# PCM2706_PCM5102A.net
KiCad netlist of a schematic drawn in EAGLE
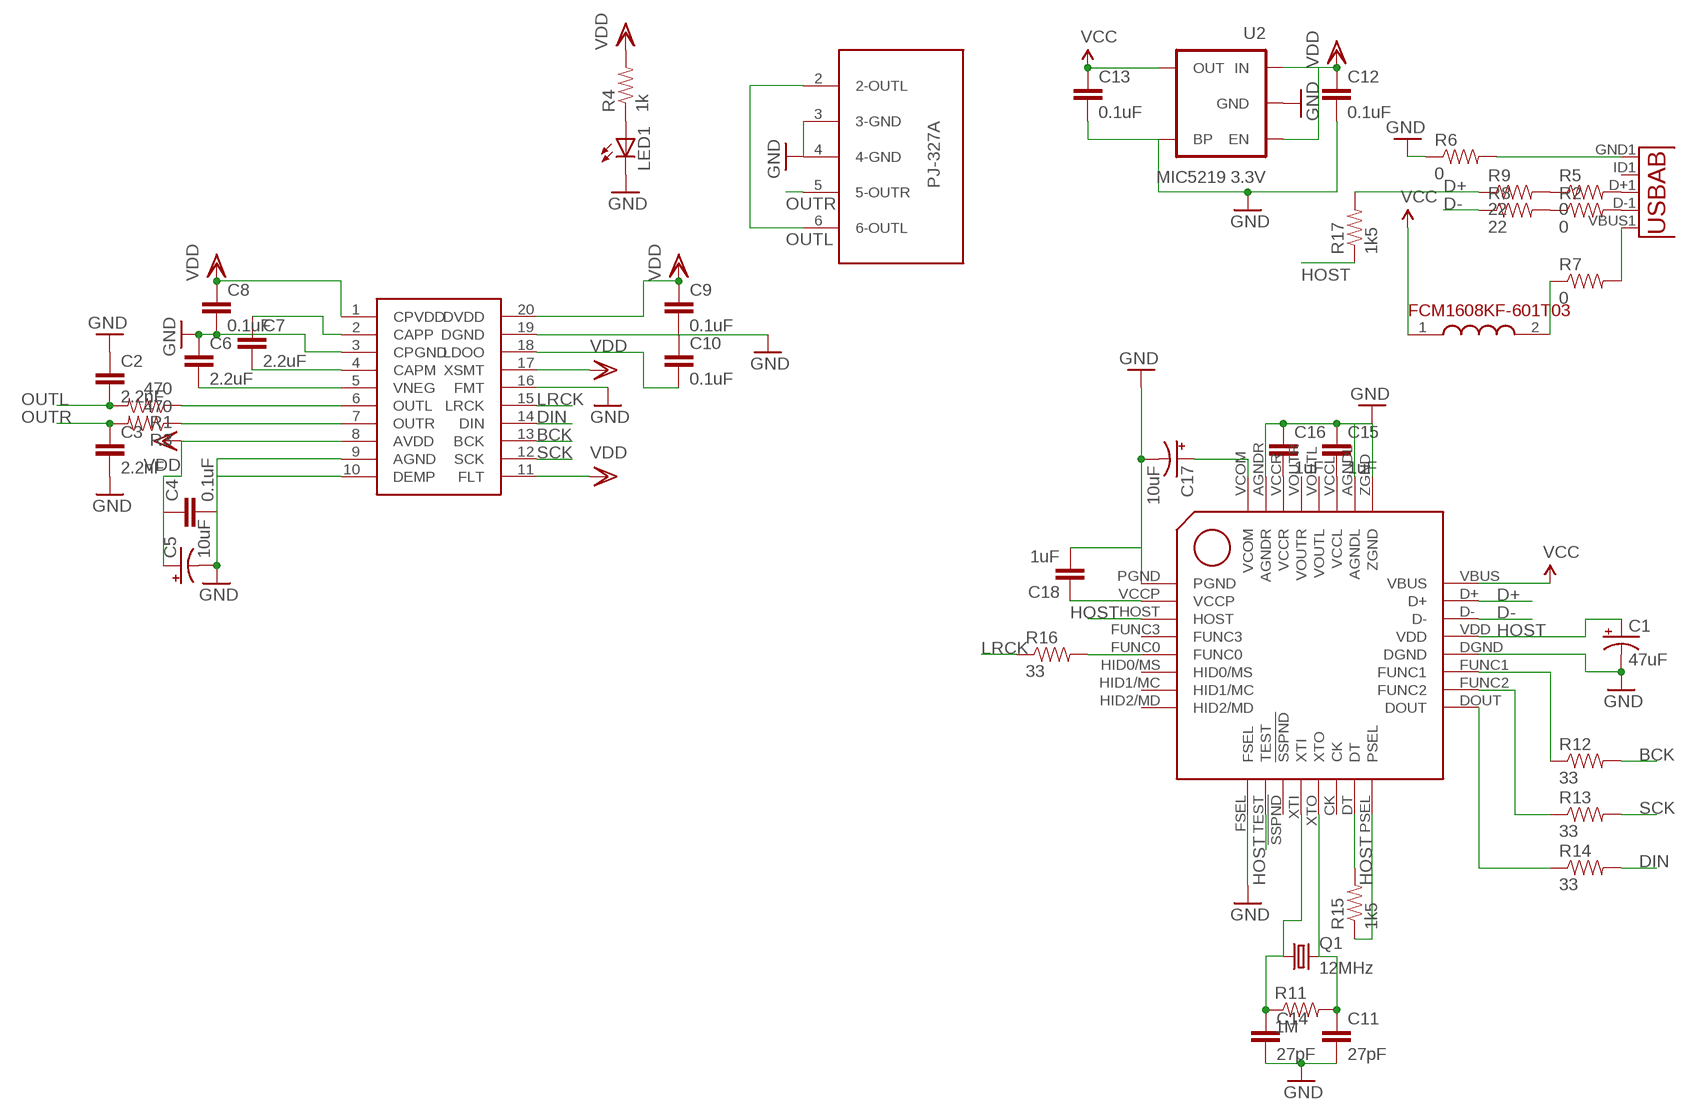
[diagram p0: schematic, sheet 1]

(export (version "E")
  (design (tool "Eeschema 10.0.6"))
  (components
    (comp (ref "C1")
      (value "47uF")
      (footprint "eagle-import:NIPPON_F80")
      (libsource (lib "eagle-import") (part "CAP_POLF80"))
    )
    (comp (ref "C2")
      (value "2.2nF")
      (footprint "eagle-import:C5B2.5")
      (libsource (lib "eagle-import") (part "C5/2.5"))
    )
    (comp (ref "C3")
      (value "2.2nF")
      (footprint "eagle-import:C5B2.5")
      (libsource (lib "eagle-import") (part "C5/2.5"))
    )
    (comp (ref "C4")
      (value "0.1uF")
      (footprint "eagle-import:1206")
      (libsource (lib "eagle-import") (part "2.2UF-CERCAP-10009"))
    )
    (comp (ref "C5")
      (value "10uF")
      (footprint "eagle-import:NIPPON_F80")
      (libsource (lib "eagle-import") (part "CAP_POLF80"))
    )
    (comp (ref "C6")
      (value "2.2uF")
      (footprint "eagle-import:1206")
      (libsource (lib "eagle-import") (part "2.2UF-CERCAP-10009"))
    )
    (comp (ref "C7")
      (value "2.2uF")
      (footprint "eagle-import:1206")
      (libsource (lib "eagle-import") (part "2.2UF-CERCAP-10009"))
    )
    (comp (ref "C8")
      (value "0.1uF")
      (footprint "eagle-import:1206")
      (libsource (lib "eagle-import") (part "2.2UF-CERCAP-10009"))
    )
    (comp (ref "C9")
      (value "0.1uF")
      (footprint "eagle-import:1206")
      (libsource (lib "eagle-import") (part "2.2UF-CERCAP-10009"))
    )
    (comp (ref "C10")
      (value "0.1uF")
      (footprint "eagle-import:1206")
      (libsource (lib "eagle-import") (part "2.2UF-CERCAP-10009"))
    )
    (comp (ref "C11")
      (value "27pF")
      (footprint "eagle-import:1206")
      (libsource (lib "eagle-import") (part "2.2UF-CERCAP-10009"))
    )
    (comp (ref "C12")
      (value "0.1uF")
      (footprint "eagle-import:1206")
      (libsource (lib "eagle-import") (part "2.2UF-CERCAP-10009"))
    )
    (comp (ref "C13")
      (value "0.1uF")
      (footprint "eagle-import:1206")
      (libsource (lib "eagle-import") (part "2.2UF-CERCAP-10009"))
    )
    (comp (ref "C14")
      (value "27pF")
      (footprint "eagle-import:1206")
      (libsource (lib "eagle-import") (part "2.2UF-CERCAP-10009"))
    )
    (comp (ref "C15")
      (value "1uF")
      (footprint "eagle-import:1206")
      (libsource (lib "eagle-import") (part "2.2UF-CERCAP-10009"))
    )
    (comp (ref "C16")
      (value "1uF")
      (footprint "eagle-import:1206")
      (libsource (lib "eagle-import") (part "2.2UF-CERCAP-10009"))
    )
    (comp (ref "C17")
      (value "10uF")
      (footprint "eagle-import:NIPPON_F80")
      (libsource (lib "eagle-import") (part "CAP_POLF80"))
    )
    (comp (ref "C18")
      (value "1uF")
      (footprint "eagle-import:1206")
      (libsource (lib "eagle-import") (part "2.2UF-CERCAP-10009"))
    )
    (comp (ref "LED1")
      (value "LEDCHIP-LED0805")
      (footprint "eagle-import:CHIP-LED0805")
      (libsource (lib "eagle-import") (part "LEDCHIP-LED0805"))
    )
    (comp (ref "Q1")
      (value "12MHz")
      (footprint "eagle-import:SM49")
      (libsource (lib "eagle-import") (part "CRYSTALSM49"))
    )
    (comp (ref "R1")
      (value "470")
      (footprint "eagle-import:1206")
      (libsource (lib "eagle-import") (part "RESISTOR1206"))
    )
    (comp (ref "R2")
      (value "0")
      (footprint "eagle-import:0805")
      (libsource (lib "eagle-import") (part "RESISTOR0805-RES"))
    )
    (comp (ref "R3")
      (value "470")
      (footprint "eagle-import:1206")
      (libsource (lib "eagle-import") (part "RESISTOR1206"))
    )
    (comp (ref "R4")
      (value "1k")
      (footprint "eagle-import:1206")
      (libsource (lib "eagle-import") (part "RESISTOR1206"))
    )
    (comp (ref "R5")
      (value "0")
      (footprint "eagle-import:0805")
      (libsource (lib "eagle-import") (part "RESISTOR0805-RES"))
    )
    (comp (ref "R6")
      (value "0")
      (footprint "eagle-import:0805")
      (libsource (lib "eagle-import") (part "RESISTOR0805-RES"))
    )
    (comp (ref "R7")
      (value "0")
      (footprint "eagle-import:0805")
      (libsource (lib "eagle-import") (part "RESISTOR0805-RES"))
    )
    (comp (ref "R8")
      (value "22")
      (footprint "eagle-import:0805")
      (libsource (lib "eagle-import") (part "RESISTOR0805-RES"))
    )
    (comp (ref "R9")
      (value "22")
      (footprint "eagle-import:0805")
      (libsource (lib "eagle-import") (part "RESISTOR0805-RES"))
    )
    (comp (ref "R11")
      (value "1M")
      (footprint "eagle-import:0805")
      (libsource (lib "eagle-import") (part "RESISTOR0805-RES"))
    )
    (comp (ref "R12")
      (value "33")
      (footprint "eagle-import:0805")
      (libsource (lib "eagle-import") (part "RESISTOR0805-RES"))
    )
    (comp (ref "R13")
      (value "33")
      (footprint "eagle-import:0805")
      (libsource (lib "eagle-import") (part "RESISTOR0805-RES"))
    )
    (comp (ref "R14")
      (value "33")
      (footprint "eagle-import:0805")
      (libsource (lib "eagle-import") (part "RESISTOR0805-RES"))
    )
    (comp (ref "R15")
      (value "1k5")
      (footprint "eagle-import:0805")
      (libsource (lib "eagle-import") (part "RESISTOR0805-RES"))
    )
    (comp (ref "R16")
      (value "33")
      (footprint "eagle-import:0805")
      (libsource (lib "eagle-import") (part "RESISTOR0805-RES"))
    )
    (comp (ref "R17")
      (value "1k5")
      (footprint "eagle-import:0805")
      (libsource (lib "eagle-import") (part "RESISTOR0805-RES"))
    )
    (comp (ref "U$1")
      (value "PCM5102")
      (footprint "eagle-import:TSSOP20")
      (libsource (lib "eagle-import") (part "PCM5102"))
    )
    (comp (ref "U$2")
      (value "PJ-327A")
      (footprint "eagle-import:PJ-327A")
      (libsource (lib "eagle-import") (part "PJ-327A"))
    )
    (comp (ref "U$3")
      (value "PCM2706")
      (footprint "eagle-import:TQFP32-08")
      (libsource (lib "eagle-import") (part "PCM2706"))
    )
    (comp (ref "U$4")
      (value "FCM1608KF-601T03")
      (footprint "eagle-import:FCM1608KF-601T03")
      (libsource (lib "eagle-import") (part "FCM1608KF-601T03"))
    )
    (comp (ref "U1")
      (value "USB\"\"")
      (footprint "eagle-import:USB-MICRO-SMD")
      (libsource (lib "eagle-import") (part "USB{dblquote}{dblquote}"))
    )
    (comp (ref "U2")
      (value "MIC5219 3.3V")
      (footprint "eagle-import:SOT23-5")
      (libsource (lib "eagle-import") (part "V_REG_MIC52193.3V"))
    )
  )
  (nets
    (net (code "1") (name "/BCK") (class "Default")
      (node (ref "R12") (pin "2") (pinfunction "2_2") (pintype "passive"))
      (node (ref "U$1") (pin "13") (pinfunction "BCK_13") (pintype "bidirectional"))
    )
    (net (code "2") (name "/D+") (class "Default")
      (node (ref "R17") (pin "2") (pinfunction "2_2") (pintype "passive"))
      (node (ref "R9") (pin "1") (pinfunction "1_1") (pintype "passive"))
      (node (ref "U$3") (pin "D+") (pinfunction "D+_D+") (pintype "bidirectional"))
    )
    (net (code "3") (name "/D-") (class "Default")
      (node (ref "R8") (pin "1") (pinfunction "1_1") (pintype "passive"))
      (node (ref "U$3") (pin "D-") (pinfunction "D-_D-") (pintype "bidirectional"))
    )
    (net (code "4") (name "/DIN") (class "Default")
      (node (ref "R14") (pin "2") (pinfunction "2_2") (pintype "passive"))
      (node (ref "U$1") (pin "14") (pinfunction "DIN_14") (pintype "bidirectional"))
    )
    (net (code "5") (name "/HOST") (class "Default")
      (node (ref "C1") (pin "+") (pinfunction "+_+") (pintype "passive"))
      (node (ref "R15") (pin "1") (pinfunction "1_1") (pintype "passive"))
      (node (ref "R17") (pin "1") (pinfunction "1_1") (pintype "passive"))
      (node (ref "U$3") (pin "HOST") (pinfunction "HOST_HOST") (pintype "power_in"))
      (node (ref "U$3") (pin "PSEL") (pinfunction "PSEL_PSEL") (pintype "bidirectional"))
      (node (ref "U$3") (pin "TEST") (pinfunction "TEST_TEST") (pintype "bidirectional"))
      (node (ref "U$3") (pin "VDD") (pinfunction "VDD_VDD") (pintype "power_in"))
    )
    (net (code "6") (name "/LRCK") (class "Default")
      (node (ref "R16") (pin "1") (pinfunction "1_1") (pintype "passive"))
      (node (ref "U$1") (pin "15") (pinfunction "LRCK_15") (pintype "bidirectional"))
    )
    (net (code "7") (name "/OUTL") (class "Default")
      (node (ref "C2") (pin "2") (pinfunction "2_2") (pintype "passive"))
      (node (ref "R1") (pin "2") (pinfunction "2_2") (pintype "passive"))
      (node (ref "U$2") (pin "2") (pinfunction "2-OUTL_2") (pintype "bidirectional"))
      (node (ref "U$2") (pin "6") (pinfunction "6-OUTL_6") (pintype "bidirectional"))
    )
    (net (code "8") (name "/OUTR") (class "Default")
      (node (ref "C3") (pin "1") (pinfunction "1_1") (pintype "passive"))
      (node (ref "R3") (pin "2") (pinfunction "2_2") (pintype "passive"))
      (node (ref "U$2") (pin "5") (pinfunction "5-OUTR_5") (pintype "bidirectional"))
    )
    (net (code "9") (name "/SCK") (class "Default")
      (node (ref "R13") (pin "2") (pinfunction "2_2") (pintype "passive"))
      (node (ref "U$1") (pin "12") (pinfunction "SCK_12") (pintype "bidirectional"))
    )
    (net (code "10") (name "GND") (class "Default")
      (node (ref "C1") (pin "-") (pinfunction "-_-") (pintype "passive"))
      (node (ref "C10") (pin "1") (pinfunction "1_1") (pintype "passive"))
      (node (ref "C11") (pin "2") (pinfunction "2_2") (pintype "passive"))
      (node (ref "C12") (pin "2") (pinfunction "2_2") (pintype "passive"))
      (node (ref "C13") (pin "2") (pinfunction "2_2") (pintype "passive"))
      (node (ref "C14") (pin "2") (pinfunction "2_2") (pintype "passive"))
      (node (ref "C15") (pin "1") (pinfunction "1_1") (pintype "passive"))
      (node (ref "C16") (pin "1") (pinfunction "1_1") (pintype "passive"))
      (node (ref "C17") (pin "-") (pinfunction "-_-") (pintype "passive"))
      (node (ref "C18") (pin "2") (pinfunction "2_2") (pintype "passive"))
      (node (ref "C2") (pin "1") (pinfunction "1_1") (pintype "passive"))
      (node (ref "C3") (pin "2") (pinfunction "2_2") (pintype "passive"))
      (node (ref "C4") (pin "2") (pinfunction "2_2") (pintype "passive"))
      (node (ref "C5") (pin "-") (pinfunction "-_-") (pintype "passive"))
      (node (ref "C6") (pin "1") (pinfunction "1_1") (pintype "passive"))
      (node (ref "C8") (pin "2") (pinfunction "2_2") (pintype "passive"))
      (node (ref "C9") (pin "2") (pinfunction "2_2") (pintype "passive"))
      (node (ref "LED1") (pin "C") (pinfunction "C_C") (pintype "passive"))
      (node (ref "R6") (pin "1") (pinfunction "1_1") (pintype "passive"))
      (node (ref "U$1") (pin "10") (pinfunction "DEMP_10") (pintype "bidirectional"))
      (node (ref "U$1") (pin "16") (pinfunction "FMT_16") (pintype "bidirectional"))
      (node (ref "U$1") (pin "19") (pinfunction "DGND_19") (pintype "bidirectional"))
      (node (ref "U$1") (pin "3") (pinfunction "CPGND_3") (pintype "bidirectional"))
      (node (ref "U$1") (pin "9") (pinfunction "AGND_9") (pintype "bidirectional"))
      (node (ref "U$2") (pin "3") (pinfunction "3-GND_3") (pintype "bidirectional"))
      (node (ref "U$2") (pin "4") (pinfunction "4-GND_4") (pintype "bidirectional"))
      (node (ref "U$3") (pin "AGNDL") (pinfunction "AGNDL_AGNDL") (pintype "power_in"))
      (node (ref "U$3") (pin "AGNDR") (pinfunction "AGNDR_AGNDR") (pintype "power_in"))
      (node (ref "U$3") (pin "DGND") (pinfunction "DGND_DGND") (pintype "power_in"))
      (node (ref "U$3") (pin "FSEL") (pinfunction "FSEL_FSEL") (pintype "bidirectional"))
      (node (ref "U$3") (pin "PGND") (pinfunction "PGND_PGND") (pintype "power_in"))
      (node (ref "U$3") (pin "ZGND") (pinfunction "ZGND_ZGND") (pintype "power_in"))
      (node (ref "U2") (pin "2") (pinfunction "GND_2") (pintype "input"))
      (node (ref "U2") (pin "4") (pinfunction "BP_4") (pintype "input"))
    )
    (net (code "11") (name "Net-(C11-Pad1)") (class "Default")
      (node (ref "C11") (pin "1") (pinfunction "1_1") (pintype "passive"))
      (node (ref "Q1") (pin "2") (pinfunction "2_2") (pintype "passive"))
      (node (ref "R11") (pin "2") (pinfunction "2_2") (pintype "passive"))
      (node (ref "U$3") (pin "XTO") (pinfunction "XTO_XTO") (pintype "bidirectional"))
    )
    (net (code "12") (name "Net-(C14-Pad1)") (class "Default")
      (node (ref "C14") (pin "1") (pinfunction "1_1") (pintype "passive"))
      (node (ref "Q1") (pin "1") (pinfunction "1_1") (pintype "passive"))
      (node (ref "R11") (pin "1") (pinfunction "1_1") (pintype "passive"))
      (node (ref "U$3") (pin "XTI") (pinfunction "XTI_XTI") (pintype "bidirectional"))
    )
    (net (code "13") (name "Net-(C15-Pad2)") (class "Default")
      (node (ref "C15") (pin "2") (pinfunction "2_2") (pintype "passive"))
      (node (ref "U$3") (pin "VCCL") (pinfunction "VCCL_VCCL") (pintype "power_in"))
    )
    (net (code "14") (name "Net-(C16-Pad2)") (class "Default")
      (node (ref "C16") (pin "2") (pinfunction "2_2") (pintype "passive"))
      (node (ref "U$3") (pin "VCCR") (pinfunction "VCCR_VCCR") (pintype "power_in"))
    )
    (net (code "15") (name "Net-(C17-Pad+)") (class "Default")
      (node (ref "C17") (pin "+") (pinfunction "+_+") (pintype "passive"))
      (node (ref "U$3") (pin "VCOM") (pinfunction "VCOM_VCOM") (pintype "power_in"))
    )
    (net (code "16") (name "Net-(C18-Pad1)") (class "Default")
      (node (ref "C18") (pin "1") (pinfunction "1_1") (pintype "passive"))
      (node (ref "U$3") (pin "VCCP") (pinfunction "VCCP_VCCP") (pintype "power_in"))
    )
    (net (code "17") (name "Net-(LED1-PadA)") (class "Default")
      (node (ref "LED1") (pin "A") (pinfunction "A_A") (pintype "passive"))
      (node (ref "R4") (pin "1") (pinfunction "1_1") (pintype "passive"))
    )
    (net (code "18") (name "Net-(R2-Pad1)") (class "Default")
      (node (ref "R2") (pin "1") (pinfunction "1_1") (pintype "passive"))
      (node (ref "R8") (pin "2") (pinfunction "2_2") (pintype "passive"))
    )
    (net (code "19") (name "Net-(R5-Pad1)") (class "Default")
      (node (ref "R5") (pin "1") (pinfunction "1_1") (pintype "passive"))
      (node (ref "R9") (pin "2") (pinfunction "2_2") (pintype "passive"))
    )
    (net (code "20") (name "Net-(R12-Pad1)") (class "Default")
      (node (ref "R12") (pin "1") (pinfunction "1_1") (pintype "passive"))
      (node (ref "U$3") (pin "FUNC1") (pinfunction "FUNC1_FUNC1") (pintype "bidirectional"))
    )
    (net (code "21") (name "Net-(R13-Pad1)") (class "Default")
      (node (ref "R13") (pin "1") (pinfunction "1_1") (pintype "passive"))
      (node (ref "U$3") (pin "FUNC2") (pinfunction "FUNC2_FUNC2") (pintype "bidirectional"))
    )
    (net (code "22") (name "Net-(R14-Pad1)") (class "Default")
      (node (ref "R14") (pin "1") (pinfunction "1_1") (pintype "passive"))
      (node (ref "U$3") (pin "DOUT") (pinfunction "DOUT_DOUT") (pintype "bidirectional"))
    )
    (net (code "23") (name "Net-(R15-Pad2)") (class "Default")
      (node (ref "R15") (pin "2") (pinfunction "2_2") (pintype "passive"))
      (node (ref "U$3") (pin "DT") (pinfunction "DT_DT") (pintype "bidirectional"))
    )
    (net (code "24") (name "Net-(R16-Pad2)") (class "Default")
      (node (ref "R16") (pin "2") (pinfunction "2_2") (pintype "passive"))
      (node (ref "U$3") (pin "FUNC0") (pinfunction "FUNC0_FUNC0") (pintype "bidirectional"))
    )
    (net (code "25") (name "Net-(U$1-CAPM)") (class "Default")
      (node (ref "C7") (pin "2") (pinfunction "2_2") (pintype "passive"))
      (node (ref "U$1") (pin "4") (pinfunction "CAPM_4") (pintype "bidirectional"))
    )
    (net (code "26") (name "Net-(U$1-CAPP)") (class "Default")
      (node (ref "C7") (pin "1") (pinfunction "1_1") (pintype "passive"))
      (node (ref "U$1") (pin "2") (pinfunction "CAPP_2") (pintype "bidirectional"))
    )
    (net (code "27") (name "Net-(U$1-LDOO)") (class "Default")
      (node (ref "C10") (pin "2") (pinfunction "2_2") (pintype "passive"))
      (node (ref "U$1") (pin "18") (pinfunction "LDOO_18") (pintype "bidirectional"))
    )
    (net (code "28") (name "Net-(U$1-OUTL)") (class "Default")
      (node (ref "R1") (pin "1") (pinfunction "1_1") (pintype "passive"))
      (node (ref "U$1") (pin "6") (pinfunction "OUTL_6") (pintype "bidirectional"))
    )
    (net (code "29") (name "Net-(U$1-OUTR)") (class "Default")
      (node (ref "R3") (pin "1") (pinfunction "1_1") (pintype "passive"))
      (node (ref "U$1") (pin "7") (pinfunction "OUTR_7") (pintype "bidirectional"))
    )
    (net (code "30") (name "Net-(U$1-VNEG)") (class "Default")
      (node (ref "C6") (pin "2") (pinfunction "2_2") (pintype "passive"))
      (node (ref "U$1") (pin "5") (pinfunction "VNEG_5") (pintype "bidirectional"))
    )
    (net (code "31") (name "Net-(U$4-2.OUT)") (class "Default")
      (node (ref "R7") (pin "1") (pinfunction "1_1") (pintype "passive"))
      (node (ref "U$4") (pin "2") (pinfunction "2.OUT_2") (pintype "bidirectional"))
    )
    (net (code "32") (name "Net-(U1-D+)") (class "Default")
      (node (ref "R5") (pin "2") (pinfunction "2_2") (pintype "passive"))
      (node (ref "U1") (pin "D+1") (pinfunction "D+_D+1") (pintype "bidirectional"))
    )
    (net (code "33") (name "Net-(U1-D-)") (class "Default")
      (node (ref "R2") (pin "2") (pinfunction "2_2") (pintype "passive"))
      (node (ref "U1") (pin "D-1") (pinfunction "D-_D-1") (pintype "bidirectional"))
    )
    (net (code "34") (name "Net-(U1-GND)") (class "Default")
      (node (ref "R6") (pin "2") (pinfunction "2_2") (pintype "passive"))
      (node (ref "U1") (pin "GND1") (pinfunction "GND_GND1") (pintype "bidirectional"))
    )
    (net (code "35") (name "Net-(U1-VBUS)") (class "Default")
      (node (ref "R7") (pin "2") (pinfunction "2_2") (pintype "passive"))
      (node (ref "U1") (pin "VBUS1") (pinfunction "VBUS_VBUS1") (pintype "bidirectional"))
    )
    (net (code "36") (name "VCC") (class "Default")
      (node (ref "C13") (pin "1") (pinfunction "1_1") (pintype "passive"))
      (node (ref "U$3") (pin "VBUS") (pinfunction "VBUS_VBUS") (pintype "power_in"))
      (node (ref "U$4") (pin "1") (pinfunction "1.IN_1") (pintype "bidirectional"))
      (node (ref "U2") (pin "5") (pinfunction "OUT_5") (pintype "passive"))
    )
    (net (code "37") (name "VDD") (class "Default")
      (node (ref "C12") (pin "1") (pinfunction "1_1") (pintype "passive"))
      (node (ref "C4") (pin "1") (pinfunction "1_1") (pintype "passive"))
      (node (ref "C5") (pin "+") (pinfunction "+_+") (pintype "passive"))
      (node (ref "C8") (pin "1") (pinfunction "1_1") (pintype "passive"))
      (node (ref "C9") (pin "1") (pinfunction "1_1") (pintype "passive"))
      (node (ref "R4") (pin "2") (pinfunction "2_2") (pintype "passive"))
      (node (ref "U$1") (pin "1") (pinfunction "CPVDD_1") (pintype "bidirectional"))
      (node (ref "U$1") (pin "11") (pinfunction "FLT_11") (pintype "bidirectional"))
      (node (ref "U$1") (pin "17") (pinfunction "XSMT_17") (pintype "bidirectional"))
      (node (ref "U$1") (pin "20") (pinfunction "DVDD_20") (pintype "bidirectional"))
      (node (ref "U$1") (pin "8") (pinfunction "AVDD_8") (pintype "bidirectional"))
      (node (ref "U2") (pin "1") (pinfunction "IN_1") (pintype "input"))
      (node (ref "U2") (pin "3") (pinfunction "EN_3") (pintype "input"))
    )
    (net (code "38") (name "unconnected-(U$3-PadCK)") (class "Default")
      (node (ref "U$3") (pin "CK") (pinfunction "CK_CK") (pintype "bidirectional"))
    )
    (net (code "39") (name "unconnected-(U$3-PadFUNC3)") (class "Default")
      (node (ref "U$3") (pin "FUNC3") (pinfunction "FUNC3_FUNC3") (pintype "bidirectional"))
    )
    (net (code "40") (name "unconnected-(U$3-PadHID0{slash}MS)") (class "Default")
      (node (ref "U$3") (pin "HID0/MS") (pinfunction "HID0/MS_HID0/MS") (pintype "bidirectional"))
    )
    (net (code "41") (name "unconnected-(U$3-PadHID1{slash}MC)") (class "Default")
      (node (ref "U$3") (pin "HID1/MC") (pinfunction "HID1/MC_HID1/MC") (pintype "bidirectional"))
    )
    (net (code "42") (name "unconnected-(U$3-PadHID2{slash}MD)") (class "Default")
      (node (ref "U$3") (pin "HID2/MD") (pinfunction "HID2/MD_HID2/MD") (pintype "bidirectional"))
    )
    (net (code "43") (name "unconnected-(U$3-PadVOUTL)") (class "Default")
      (node (ref "U$3") (pin "VOUTL") (pinfunction "VOUTL_VOUTL") (pintype "output"))
    )
    (net (code "44") (name "unconnected-(U$3-PadVOUTR)") (class "Default")
      (node (ref "U$3") (pin "VOUTR") (pinfunction "VOUTR_VOUTR") (pintype "output"))
    )
    (net (code "45") (name "unconnected-(U$3-~{SSPND}-Pad!SSPND)") (class "Default")
      (node (ref "U$3") (pin "!SSPND") (pinfunction "~{SSPND}_!SSPND") (pintype "bidirectional"))
    )
    (net (code "46") (name "unconnected-(U1-USBID-PadID1)") (class "Default")
      (node (ref "U1") (pin "ID1") (pinfunction "USBID_ID1") (pintype "bidirectional"))
    )
  )
)
